# PC_Microcontroller_IOIfaces.net
KiCad netlist of a schematic drawn in Altium Designer
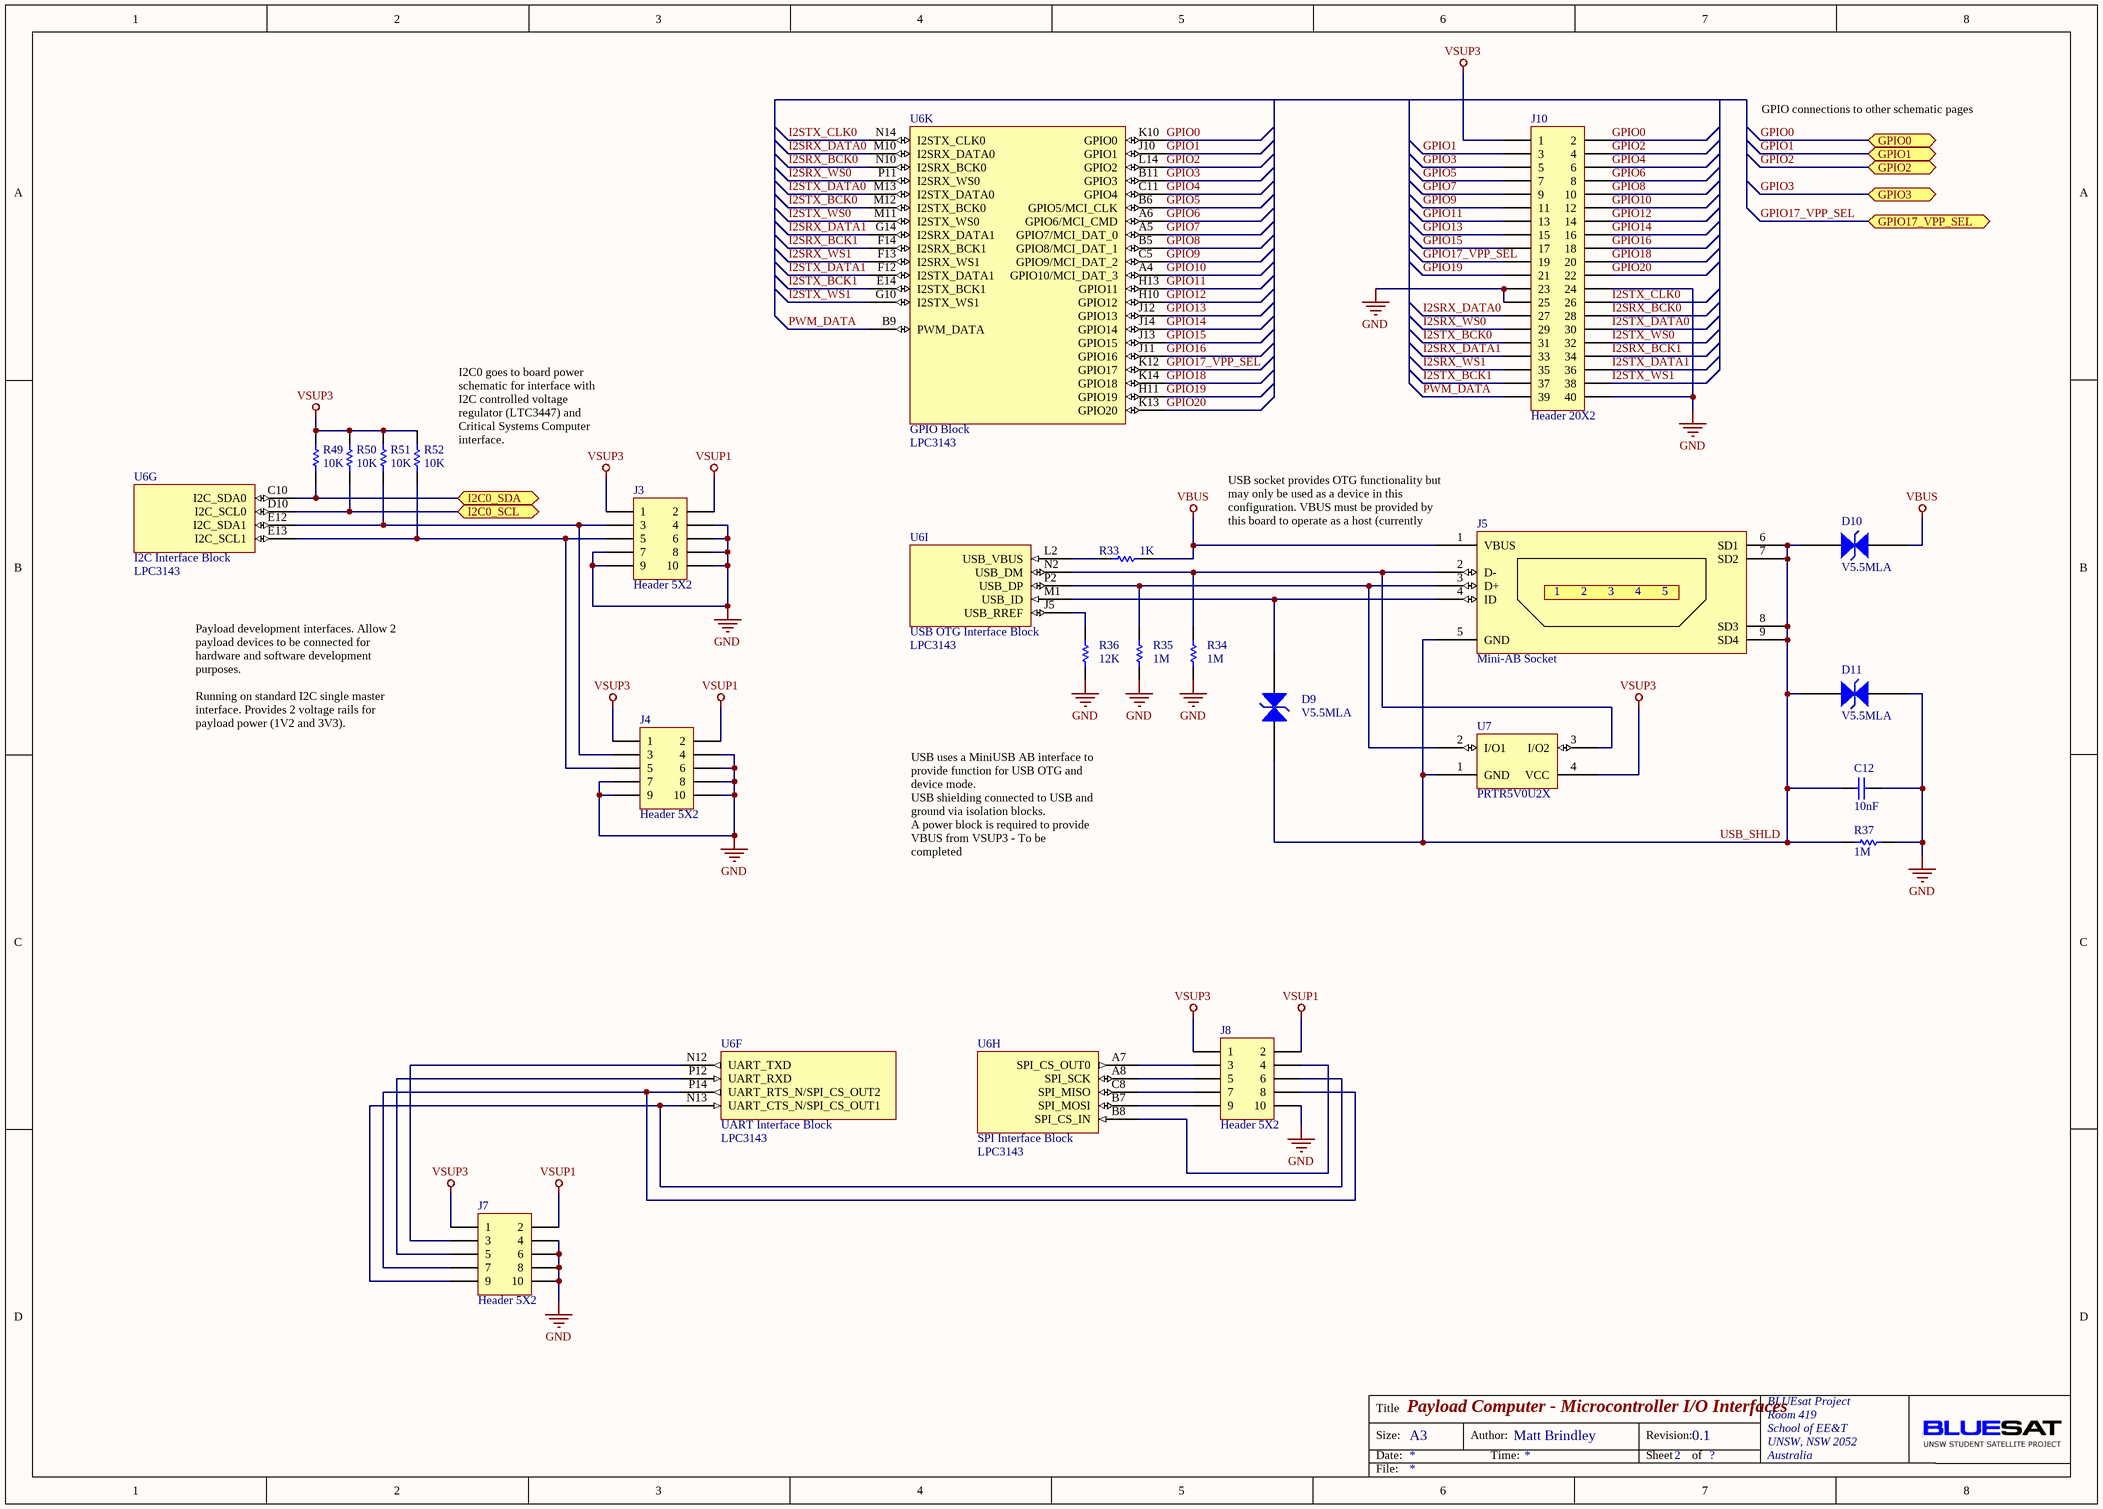
[diagram p0: PC_Microcontroller_IOIfaces.SchDoc]

(export (version "E")
  (design (tool "Eeschema 10.0.6"))
  (components
    (comp (ref "C12")
      (value "10nF")
      (footprint "C0805")
      (description "Capacitor (Semiconductor SIM Model)")
      (fields (field (name "Comment") "Cap Semi") (field (name "PUBLISHER") "Altium Limited"))
      (libsource (lib "Miscellaneous Devices") (part "Cap Semi"))
    )
    (comp (ref "D9")
      (value "V5.5MLA")
      (footprint "MLA-1206")
      (description "Multilayer varistor - Transient voltage protection device")
      (fields (field (name "PUBLISHER") "Altium Limited"))
      (libsource (lib "PC_Components") (part "V5.5MLA0603"))
    )
    (comp (ref "D10")
      (value "V5.5MLA")
      (footprint "MLA-1206")
      (description "Multilayer varistor - Transient voltage protection device")
      (fields (field (name "PUBLISHER") "Altium Limited"))
      (libsource (lib "PC_Components") (part "V5.5MLA0603"))
    )
    (comp (ref "D11")
      (value "V5.5MLA")
      (footprint "MLA-1206")
      (description "Multilayer varistor - Transient voltage protection device")
      (fields (field (name "PUBLISHER") "Altium Limited"))
      (libsource (lib "PC_Components") (part "V5.5MLA0603"))
    )
    (comp (ref "J3")
      (value "Header 5X2")
      (footprint "HDR2X5")
      (description "Header, 5-Pin, Dual row")
      (fields (field (name "PUBLISHER") "Altium Limited"))
      (libsource (lib "Miscellaneous Connectors") (part "Header 5X2"))
    )
    (comp (ref "J4")
      (value "Header 5X2")
      (footprint "HDR2X5")
      (description "Header, 5-Pin, Dual row")
      (fields (field (name "PUBLISHER") "Altium Limited"))
      (libsource (lib "Miscellaneous Connectors") (part "Header 5X2"))
    )
    (comp (ref "J5")
      (value "Mini-AB Socket")
      (footprint "miniUSB-AB")
      (description "MiniUSB AB type socket")
      (fields (field (name "PUBLISHER") "Altium Limited"))
      (libsource (lib "PC_Components") (part "miniUSB-AB"))
    )
    (comp (ref "J7")
      (value "Header 5X2")
      (footprint "HDR2X5")
      (description "Header, 5-Pin, Dual row")
      (fields (field (name "PUBLISHER") "Altium Limited"))
      (libsource (lib "Miscellaneous Connectors") (part "Header 5X2"))
    )
    (comp (ref "J8")
      (value "Header 5X2")
      (footprint "HDR2X5")
      (description "Header, 5-Pin, Dual row")
      (fields (field (name "PUBLISHER") "Altium Limited"))
      (libsource (lib "Miscellaneous Connectors") (part "Header 5X2"))
    )
    (comp (ref "J10")
      (value "Header 20X2")
      (footprint "HDR2X20")
      (description "Header, 20-Pin, Dual row")
      (fields (field (name "PUBLISHER") "Altium Limited"))
      (libsource (lib "Miscellaneous Connectors") (part "Header 20X2"))
    )
    (comp (ref "R33")
      (value "1K")
      (footprint "6-0805_L")
      (description "Semiconductor Resistor")
      (fields (field (name "Comment") "Res Semi") (field (name "PUBLISHER") "Altium Limited"))
      (libsource (lib "Miscellaneous Devices") (part "Res Semi"))
    )
    (comp (ref "R34")
      (value "1M")
      (footprint "6-0805_L")
      (description "Semiconductor Resistor")
      (fields (field (name "Comment") "Res Semi") (field (name "PUBLISHER") "Altium Limited"))
      (libsource (lib "Miscellaneous Devices") (part "Res Semi"))
    )
    (comp (ref "R35")
      (value "1M")
      (footprint "6-0805_L")
      (description "Semiconductor Resistor")
      (fields (field (name "Comment") "Res Semi") (field (name "PUBLISHER") "Altium Limited"))
      (libsource (lib "Miscellaneous Devices") (part "Res Semi"))
    )
    (comp (ref "R36")
      (value "12K")
      (footprint "6-0805_L")
      (description "Semiconductor Resistor")
      (fields (field (name "Comment") "Res Semi") (field (name "PUBLISHER") "Altium Limited"))
      (libsource (lib "Miscellaneous Devices") (part "Res Semi"))
    )
    (comp (ref "R37")
      (value "1M")
      (footprint "6-0805_L")
      (description "Semiconductor Resistor")
      (fields (field (name "Comment") "Res Semi") (field (name "PUBLISHER") "Altium Limited"))
      (libsource (lib "Miscellaneous Devices") (part "Res Semi"))
    )
    (comp (ref "R49")
      (value "10K")
      (footprint "6-0805_L")
      (description "Semiconductor Resistor")
      (fields (field (name "Comment") "Res Semi") (field (name "PUBLISHER") "Altium Limited"))
      (libsource (lib "Miscellaneous Devices") (part "Res Semi"))
    )
    (comp (ref "R50")
      (value "10K")
      (footprint "6-0805_L")
      (description "Semiconductor Resistor")
      (fields (field (name "Comment") "Res Semi") (field (name "PUBLISHER") "Altium Limited"))
      (libsource (lib "Miscellaneous Devices") (part "Res Semi"))
    )
    (comp (ref "R51")
      (value "10K")
      (footprint "6-0805_L")
      (description "Semiconductor Resistor")
      (fields (field (name "Comment") "Res Semi") (field (name "PUBLISHER") "Altium Limited"))
      (libsource (lib "Miscellaneous Devices") (part "Res Semi"))
    )
    (comp (ref "R52")
      (value "10K")
      (footprint "6-0805_L")
      (description "Semiconductor Resistor")
      (fields (field (name "Comment") "Res Semi") (field (name "PUBLISHER") "Altium Limited"))
      (libsource (lib "Miscellaneous Devices") (part "Res Semi"))
    )
    (comp (ref "U6")
      (value "LPC3143")
      (footprint "PC_Footprints:BGA180C80P14X14_1200X1200X120")
      (description "NXP ARM9 based microcontroller")
      (fields (field (name "PUBLISHER") "BLUEsat Project"))
      (libsource (lib "PC_Components") (part "LPC3143"))
    )
    (comp (ref "U7")
      (value "PRTR5V0U2X")
      (footprint "SOT190P230X110-4N")
      (description "Electrostatic discharge protection diode IC - NXP")
      (fields (field (name "PUBLISHER") "Altium Limited"))
      (libsource (lib "PC_Components") (part "PRTR5V0U2X"))
    )
  )
  (nets
    (net (code "1") (name "/GPIO0") (class "Default")
      (node (ref "J10") (pin "2") (pinfunction "2_2") (pintype "passive"))
      (node (ref "U6") (pin "K10") (pinfunction "GPIO0_K10") (pintype "bidirectional"))
    )
    (net (code "2") (name "/GPIO1") (class "Default")
      (node (ref "J10") (pin "3") (pinfunction "3_3") (pintype "passive"))
      (node (ref "U6") (pin "J10") (pinfunction "GPIO1_J10") (pintype "bidirectional"))
    )
    (net (code "3") (name "/GPIO2") (class "Default")
      (node (ref "J10") (pin "4") (pinfunction "4_4") (pintype "passive"))
      (node (ref "U6") (pin "L14") (pinfunction "GPIO2_L14") (pintype "bidirectional"))
    )
    (net (code "4") (name "/GPIO3") (class "Default")
      (node (ref "J10") (pin "5") (pinfunction "5_5") (pintype "passive"))
      (node (ref "U6") (pin "B11") (pinfunction "GPIO3_B11") (pintype "bidirectional"))
    )
    (net (code "5") (name "/GPIO4") (class "Default")
      (node (ref "J10") (pin "6") (pinfunction "6_6") (pintype "passive"))
      (node (ref "U6") (pin "C11") (pinfunction "GPIO4_C11") (pintype "bidirectional"))
    )
    (net (code "6") (name "/GPIO5") (class "Default")
      (node (ref "J10") (pin "7") (pinfunction "7_7") (pintype "passive"))
      (node (ref "U6") (pin "B6") (pinfunction "GPIO5/MCI_CLK_B6") (pintype "bidirectional"))
    )
    (net (code "7") (name "/GPIO6") (class "Default")
      (node (ref "J10") (pin "8") (pinfunction "8_8") (pintype "passive"))
      (node (ref "U6") (pin "A6") (pinfunction "GPIO6/MCI_CMD_A6") (pintype "bidirectional"))
    )
    (net (code "8") (name "/GPIO7") (class "Default")
      (node (ref "J10") (pin "9") (pinfunction "9_9") (pintype "passive"))
      (node (ref "U6") (pin "A5") (pinfunction "GPIO7/MCI_DAT_0_A5") (pintype "bidirectional"))
    )
    (net (code "9") (name "/GPIO8") (class "Default")
      (node (ref "J10") (pin "10") (pinfunction "10_10") (pintype "passive"))
      (node (ref "U6") (pin "B5") (pinfunction "GPIO8/MCI_DAT_1_B5") (pintype "bidirectional"))
    )
    (net (code "10") (name "/GPIO9") (class "Default")
      (node (ref "J10") (pin "11") (pinfunction "11_11") (pintype "passive"))
      (node (ref "U6") (pin "C5") (pinfunction "GPIO9/MCI_DAT_2_C5") (pintype "bidirectional"))
    )
    (net (code "11") (name "/GPIO10") (class "Default")
      (node (ref "J10") (pin "12") (pinfunction "12_12") (pintype "passive"))
      (node (ref "U6") (pin "A4") (pinfunction "GPIO10/MCI_DAT_3_A4") (pintype "bidirectional"))
    )
    (net (code "12") (name "/GPIO11") (class "Default")
      (node (ref "J10") (pin "13") (pinfunction "13_13") (pintype "passive"))
      (node (ref "U6") (pin "H13") (pinfunction "GPIO11_H13") (pintype "bidirectional"))
    )
    (net (code "13") (name "/GPIO12") (class "Default")
      (node (ref "J10") (pin "14") (pinfunction "14_14") (pintype "passive"))
      (node (ref "U6") (pin "H10") (pinfunction "GPIO12_H10") (pintype "bidirectional"))
    )
    (net (code "14") (name "/GPIO13") (class "Default")
      (node (ref "J10") (pin "15") (pinfunction "15_15") (pintype "passive"))
      (node (ref "U6") (pin "J12") (pinfunction "GPIO13_J12") (pintype "bidirectional"))
    )
    (net (code "15") (name "/GPIO14") (class "Default")
      (node (ref "J10") (pin "16") (pinfunction "16_16") (pintype "passive"))
      (node (ref "U6") (pin "J14") (pinfunction "GPIO14_J14") (pintype "bidirectional"))
    )
    (net (code "16") (name "/GPIO15") (class "Default")
      (node (ref "J10") (pin "17") (pinfunction "17_17") (pintype "passive"))
      (node (ref "U6") (pin "J13") (pinfunction "GPIO15_J13") (pintype "bidirectional"))
    )
    (net (code "17") (name "/GPIO16") (class "Default")
      (node (ref "J10") (pin "18") (pinfunction "18_18") (pintype "passive"))
      (node (ref "U6") (pin "J11") (pinfunction "GPIO16_J11") (pintype "bidirectional"))
    )
    (net (code "18") (name "/GPIO17_VPP_SEL") (class "Default")
      (node (ref "J10") (pin "19") (pinfunction "19_19") (pintype "passive"))
      (node (ref "U6") (pin "K12") (pinfunction "GPIO17_K12") (pintype "bidirectional"))
    )
    (net (code "19") (name "/GPIO18") (class "Default")
      (node (ref "J10") (pin "20") (pinfunction "20_20") (pintype "passive"))
      (node (ref "U6") (pin "K14") (pinfunction "GPIO18_K14") (pintype "bidirectional"))
    )
    (net (code "20") (name "/GPIO19") (class "Default")
      (node (ref "J10") (pin "21") (pinfunction "21_21") (pintype "passive"))
      (node (ref "U6") (pin "H11") (pinfunction "GPIO19_H11") (pintype "bidirectional"))
    )
    (net (code "21") (name "/GPIO20") (class "Default")
      (node (ref "J10") (pin "22") (pinfunction "22_22") (pintype "passive"))
      (node (ref "U6") (pin "K13") (pinfunction "GPIO20_K13") (pintype "bidirectional"))
    )
    (net (code "22") (name "/I2C0_SCL") (class "Default")
      (node (ref "R50") (pin "1") (pinfunction "1_1") (pintype "passive"))
      (node (ref "U6") (pin "D10") (pinfunction "I2C_SCL0_D10") (pintype "bidirectional"))
    )
    (net (code "23") (name "/I2C0_SDA") (class "Default")
      (node (ref "R49") (pin "1") (pinfunction "1_1") (pintype "passive"))
      (node (ref "U6") (pin "C10") (pinfunction "I2C_SDA0_C10") (pintype "bidirectional"))
    )
    (net (code "24") (name "/I2SRX_BCK0") (class "Default")
      (node (ref "J10") (pin "28") (pinfunction "28_28") (pintype "passive"))
      (node (ref "U6") (pin "N10") (pinfunction "I2SRX_BCK0_N10") (pintype "bidirectional"))
    )
    (net (code "25") (name "/I2SRX_BCK1") (class "Default")
      (node (ref "J10") (pin "34") (pinfunction "34_34") (pintype "passive"))
      (node (ref "U6") (pin "F14") (pinfunction "I2SRX_BCK1_F14") (pintype "bidirectional"))
    )
    (net (code "26") (name "/I2SRX_DATA0") (class "Default")
      (node (ref "J10") (pin "27") (pinfunction "27_27") (pintype "passive"))
      (node (ref "U6") (pin "M10") (pinfunction "I2SRX_DATA0_M10") (pintype "bidirectional"))
    )
    (net (code "27") (name "/I2SRX_DATA1") (class "Default")
      (node (ref "J10") (pin "33") (pinfunction "33_33") (pintype "passive"))
      (node (ref "U6") (pin "G14") (pinfunction "I2SRX_DATA1_G14") (pintype "bidirectional"))
    )
    (net (code "28") (name "/I2SRX_WS0") (class "Default")
      (node (ref "J10") (pin "29") (pinfunction "29_29") (pintype "passive"))
      (node (ref "U6") (pin "P11") (pinfunction "I2SRX_WS0_P11") (pintype "bidirectional"))
    )
    (net (code "29") (name "/I2SRX_WS1") (class "Default")
      (node (ref "J10") (pin "35") (pinfunction "35_35") (pintype "passive"))
      (node (ref "U6") (pin "F13") (pinfunction "I2SRX_WS1_F13") (pintype "bidirectional"))
    )
    (net (code "30") (name "/I2STX_BCK0") (class "Default")
      (node (ref "J10") (pin "31") (pinfunction "31_31") (pintype "passive"))
      (node (ref "U6") (pin "M12") (pinfunction "I2STX_BCK0_M12") (pintype "bidirectional"))
    )
    (net (code "31") (name "/I2STX_BCK1") (class "Default")
      (node (ref "J10") (pin "37") (pinfunction "37_37") (pintype "passive"))
      (node (ref "U6") (pin "E14") (pinfunction "I2STX_BCK1_E14") (pintype "bidirectional"))
    )
    (net (code "32") (name "/I2STX_CLK0") (class "Default")
      (node (ref "J10") (pin "26") (pinfunction "26_26") (pintype "passive"))
      (node (ref "U6") (pin "N14") (pinfunction "I2STX_CLK0_N14") (pintype "bidirectional"))
    )
    (net (code "33") (name "/I2STX_DATA0") (class "Default")
      (node (ref "J10") (pin "30") (pinfunction "30_30") (pintype "passive"))
      (node (ref "U6") (pin "M13") (pinfunction "I2STX_DATA0_M13") (pintype "bidirectional"))
    )
    (net (code "34") (name "/I2STX_DATA1") (class "Default")
      (node (ref "J10") (pin "36") (pinfunction "36_36") (pintype "passive"))
      (node (ref "U6") (pin "F12") (pinfunction "I2STX_DATA1_F12") (pintype "bidirectional"))
    )
    (net (code "35") (name "/I2STX_WS0") (class "Default")
      (node (ref "J10") (pin "32") (pinfunction "32_32") (pintype "passive"))
      (node (ref "U6") (pin "M11") (pinfunction "I2STX_WS0_M11") (pintype "bidirectional"))
    )
    (net (code "36") (name "/I2STX_WS1") (class "Default")
      (node (ref "J10") (pin "38") (pinfunction "38_38") (pintype "passive"))
      (node (ref "U6") (pin "G10") (pinfunction "I2STX_WS1_G10") (pintype "bidirectional"))
    )
    (net (code "37") (name "/PWM_DATA") (class "Default")
      (node (ref "J10") (pin "39") (pinfunction "39_39") (pintype "passive"))
      (node (ref "U6") (pin "B9") (pinfunction "PWM_DATA_B9") (pintype "bidirectional"))
    )
    (net (code "38") (name "/USB_SHLD") (class "Default")
      (node (ref "C12") (pin "2") (pinfunction "2_2") (pintype "passive"))
      (node (ref "D10") (pin "2") (pinfunction "2_2") (pintype "passive"))
      (node (ref "D11") (pin "2") (pinfunction "2_2") (pintype "passive"))
      (node (ref "D9") (pin "1") (pinfunction "1_1") (pintype "passive"))
      (node (ref "J5") (pin "5") (pinfunction "GND_5") (pintype "power_in"))
      (node (ref "J5") (pin "6") (pinfunction "SD1_6") (pintype "passive"))
      (node (ref "J5") (pin "7") (pinfunction "SD2_7") (pintype "passive"))
      (node (ref "J5") (pin "8") (pinfunction "SD3_8") (pintype "passive"))
      (node (ref "J5") (pin "9") (pinfunction "SD4_9") (pintype "passive"))
      (node (ref "R37") (pin "2") (pinfunction "2_2") (pintype "passive"))
      (node (ref "U7") (pin "1") (pinfunction "GND_1") (pintype "power_in"))
    )
    (net (code "39") (name "GND") (class "Default")
      (node (ref "C12") (pin "1") (pinfunction "1_1") (pintype "passive"))
      (node (ref "D11") (pin "1") (pinfunction "1_1") (pintype "passive"))
      (node (ref "J10") (pin "23") (pinfunction "23_23") (pintype "passive"))
      (node (ref "J10") (pin "24") (pinfunction "24_24") (pintype "passive"))
      (node (ref "J10") (pin "25") (pinfunction "25_25") (pintype "passive"))
      (node (ref "J10") (pin "40") (pinfunction "40_40") (pintype "passive"))
      (node (ref "J3") (pin "10") (pinfunction "10_10") (pintype "passive"))
      (node (ref "J3") (pin "4") (pinfunction "4_4") (pintype "passive"))
      (node (ref "J3") (pin "6") (pinfunction "6_6") (pintype "passive"))
      (node (ref "J3") (pin "7") (pinfunction "7_7") (pintype "passive"))
      (node (ref "J3") (pin "8") (pinfunction "8_8") (pintype "passive"))
      (node (ref "J3") (pin "9") (pinfunction "9_9") (pintype "passive"))
      (node (ref "J4") (pin "10") (pinfunction "10_10") (pintype "passive"))
      (node (ref "J4") (pin "4") (pinfunction "4_4") (pintype "passive"))
      (node (ref "J4") (pin "6") (pinfunction "6_6") (pintype "passive"))
      (node (ref "J4") (pin "7") (pinfunction "7_7") (pintype "passive"))
      (node (ref "J4") (pin "8") (pinfunction "8_8") (pintype "passive"))
      (node (ref "J4") (pin "9") (pinfunction "9_9") (pintype "passive"))
      (node (ref "J7") (pin "10") (pinfunction "10_10") (pintype "passive"))
      (node (ref "J7") (pin "4") (pinfunction "4_4") (pintype "passive"))
      (node (ref "J7") (pin "6") (pinfunction "6_6") (pintype "passive"))
      (node (ref "J7") (pin "8") (pinfunction "8_8") (pintype "passive"))
      (node (ref "J8") (pin "10") (pinfunction "10_10") (pintype "passive"))
      (node (ref "R34") (pin "1") (pinfunction "1_1") (pintype "passive"))
      (node (ref "R35") (pin "1") (pinfunction "1_1") (pintype "passive"))
      (node (ref "R36") (pin "1") (pinfunction "1_1") (pintype "passive"))
      (node (ref "R37") (pin "1") (pinfunction "1_1") (pintype "passive"))
    )
    (net (code "40") (name "Net-(J5-D+)") (class "Default")
      (node (ref "J5") (pin "3") (pinfunction "D+_3") (pintype "bidirectional"))
      (node (ref "R35") (pin "2") (pinfunction "2_2") (pintype "passive"))
      (node (ref "U6") (pin "P2") (pinfunction "USB_DP_P2") (pintype "bidirectional"))
      (node (ref "U7") (pin "2") (pinfunction "I/O1_2") (pintype "bidirectional"))
    )
    (net (code "41") (name "Net-(J5-D-)") (class "Default")
      (node (ref "J5") (pin "2") (pinfunction "D-_2") (pintype "bidirectional"))
      (node (ref "R34") (pin "2") (pinfunction "2_2") (pintype "passive"))
      (node (ref "U6") (pin "N2") (pinfunction "USB_DM_N2") (pintype "bidirectional"))
      (node (ref "U7") (pin "3") (pinfunction "I/O2_3") (pintype "bidirectional"))
    )
    (net (code "42") (name "Net-(J5-ID)") (class "Default")
      (node (ref "D9") (pin "2") (pinfunction "2_2") (pintype "passive"))
      (node (ref "J5") (pin "4") (pinfunction "ID_4") (pintype "bidirectional"))
      (node (ref "U6") (pin "M1") (pinfunction "USB_ID_M1") (pintype "input"))
    )
    (net (code "43") (name "Net-(U6F-UART_CTS_N{slash}SPI_CS_OUT1)") (class "Default")
      (node (ref "J7") (pin "9") (pinfunction "9_9") (pintype "passive"))
      (node (ref "J8") (pin "6") (pinfunction "6_6") (pintype "passive"))
      (node (ref "U6") (pin "N13") (pinfunction "UART_CTS_N/SPI_CS_OUT1_N13") (pintype "input"))
    )
    (net (code "44") (name "Net-(U6F-UART_RTS_N{slash}SPI_CS_OUT2)") (class "Default")
      (node (ref "J7") (pin "7") (pinfunction "7_7") (pintype "passive"))
      (node (ref "J8") (pin "8") (pinfunction "8_8") (pintype "passive"))
      (node (ref "U6") (pin "P14") (pinfunction "UART_RTS_N/SPI_CS_OUT2_P14") (pintype "output"))
    )
    (net (code "45") (name "Net-(U6F-UART_RXD)") (class "Default")
      (node (ref "J7") (pin "5") (pinfunction "5_5") (pintype "passive"))
      (node (ref "U6") (pin "P12") (pinfunction "UART_RXD_P12") (pintype "input"))
    )
    (net (code "46") (name "Net-(U6F-UART_TXD)") (class "Default")
      (node (ref "J7") (pin "3") (pinfunction "3_3") (pintype "passive"))
      (node (ref "U6") (pin "N12") (pinfunction "UART_TXD_N12") (pintype "output"))
    )
    (net (code "47") (name "Net-(U6G-I2C_SCL1)") (class "Default")
      (node (ref "J3") (pin "5") (pinfunction "5_5") (pintype "passive"))
      (node (ref "J4") (pin "5") (pinfunction "5_5") (pintype "passive"))
      (node (ref "R52") (pin "1") (pinfunction "1_1") (pintype "passive"))
      (node (ref "U6") (pin "E13") (pinfunction "I2C_SCL1_E13") (pintype "bidirectional"))
    )
    (net (code "48") (name "Net-(U6G-I2C_SDA1)") (class "Default")
      (node (ref "J3") (pin "3") (pinfunction "3_3") (pintype "passive"))
      (node (ref "J4") (pin "3") (pinfunction "3_3") (pintype "passive"))
      (node (ref "R51") (pin "1") (pinfunction "1_1") (pintype "passive"))
      (node (ref "U6") (pin "E12") (pinfunction "I2C_SDA1_E12") (pintype "bidirectional"))
    )
    (net (code "49") (name "Net-(U6H-SPI_CS_IN)") (class "Default")
      (node (ref "J8") (pin "4") (pinfunction "4_4") (pintype "passive"))
      (node (ref "U6") (pin "B8") (pinfunction "SPI_CS_IN_B8") (pintype "input"))
    )
    (net (code "50") (name "Net-(U6H-SPI_CS_OUT0)") (class "Default")
      (node (ref "J8") (pin "3") (pinfunction "3_3") (pintype "passive"))
      (node (ref "U6") (pin "A7") (pinfunction "SPI_CS_OUT0_A7") (pintype "output"))
    )
    (net (code "51") (name "Net-(U6H-SPI_MISO)") (class "Default")
      (node (ref "J8") (pin "7") (pinfunction "7_7") (pintype "passive"))
      (node (ref "U6") (pin "C8") (pinfunction "SPI_MISO_C8") (pintype "bidirectional"))
    )
    (net (code "52") (name "Net-(U6H-SPI_MOSI)") (class "Default")
      (node (ref "J8") (pin "9") (pinfunction "9_9") (pintype "passive"))
      (node (ref "U6") (pin "B7") (pinfunction "SPI_MOSI_B7") (pintype "bidirectional"))
    )
    (net (code "53") (name "Net-(U6H-SPI_SCK)") (class "Default")
      (node (ref "J8") (pin "5") (pinfunction "5_5") (pintype "passive"))
      (node (ref "U6") (pin "A8") (pinfunction "SPI_SCK_A8") (pintype "bidirectional"))
    )
    (net (code "54") (name "Net-(U6I-USB_RREF)") (class "Default")
      (node (ref "R36") (pin "2") (pinfunction "2_2") (pintype "passive"))
      (node (ref "U6") (pin "J5") (pinfunction "USB_RREF_J5") (pintype "bidirectional"))
    )
    (net (code "55") (name "Net-(U6I-USB_VBUS)") (class "Default")
      (node (ref "R33") (pin "1") (pinfunction "1_1") (pintype "passive"))
      (node (ref "U6") (pin "L2") (pinfunction "USB_VBUS_L2") (pintype "input"))
    )
    (net (code "56") (name "VBUS") (class "Default")
      (node (ref "D10") (pin "1") (pinfunction "1_1") (pintype "passive"))
      (node (ref "J5") (pin "1") (pinfunction "VBUS_1") (pintype "power_in"))
      (node (ref "R33") (pin "2") (pinfunction "2_2") (pintype "passive"))
    )
    (net (code "57") (name "VSUP1") (class "Default")
      (node (ref "J3") (pin "2") (pinfunction "2_2") (pintype "passive"))
      (node (ref "J4") (pin "2") (pinfunction "2_2") (pintype "passive"))
      (node (ref "J7") (pin "2") (pinfunction "2_2") (pintype "passive"))
      (node (ref "J8") (pin "2") (pinfunction "2_2") (pintype "passive"))
    )
    (net (code "58") (name "VSUP3") (class "Default")
      (node (ref "J10") (pin "1") (pinfunction "1_1") (pintype "passive"))
      (node (ref "J3") (pin "1") (pinfunction "1_1") (pintype "passive"))
      (node (ref "J4") (pin "1") (pinfunction "1_1") (pintype "passive"))
      (node (ref "J7") (pin "1") (pinfunction "1_1") (pintype "passive"))
      (node (ref "J8") (pin "1") (pinfunction "1_1") (pintype "passive"))
      (node (ref "R49") (pin "2") (pinfunction "2_2") (pintype "passive"))
      (node (ref "R50") (pin "2") (pinfunction "2_2") (pintype "passive"))
      (node (ref "R51") (pin "2") (pinfunction "2_2") (pintype "passive"))
      (node (ref "R52") (pin "2") (pinfunction "2_2") (pintype "passive"))
      (node (ref "U7") (pin "4") (pinfunction "VCC_4") (pintype "power_in"))
    )
  )
)
